# BufferSaver.net
KiCad netlist of a schematic drawn in EAGLE
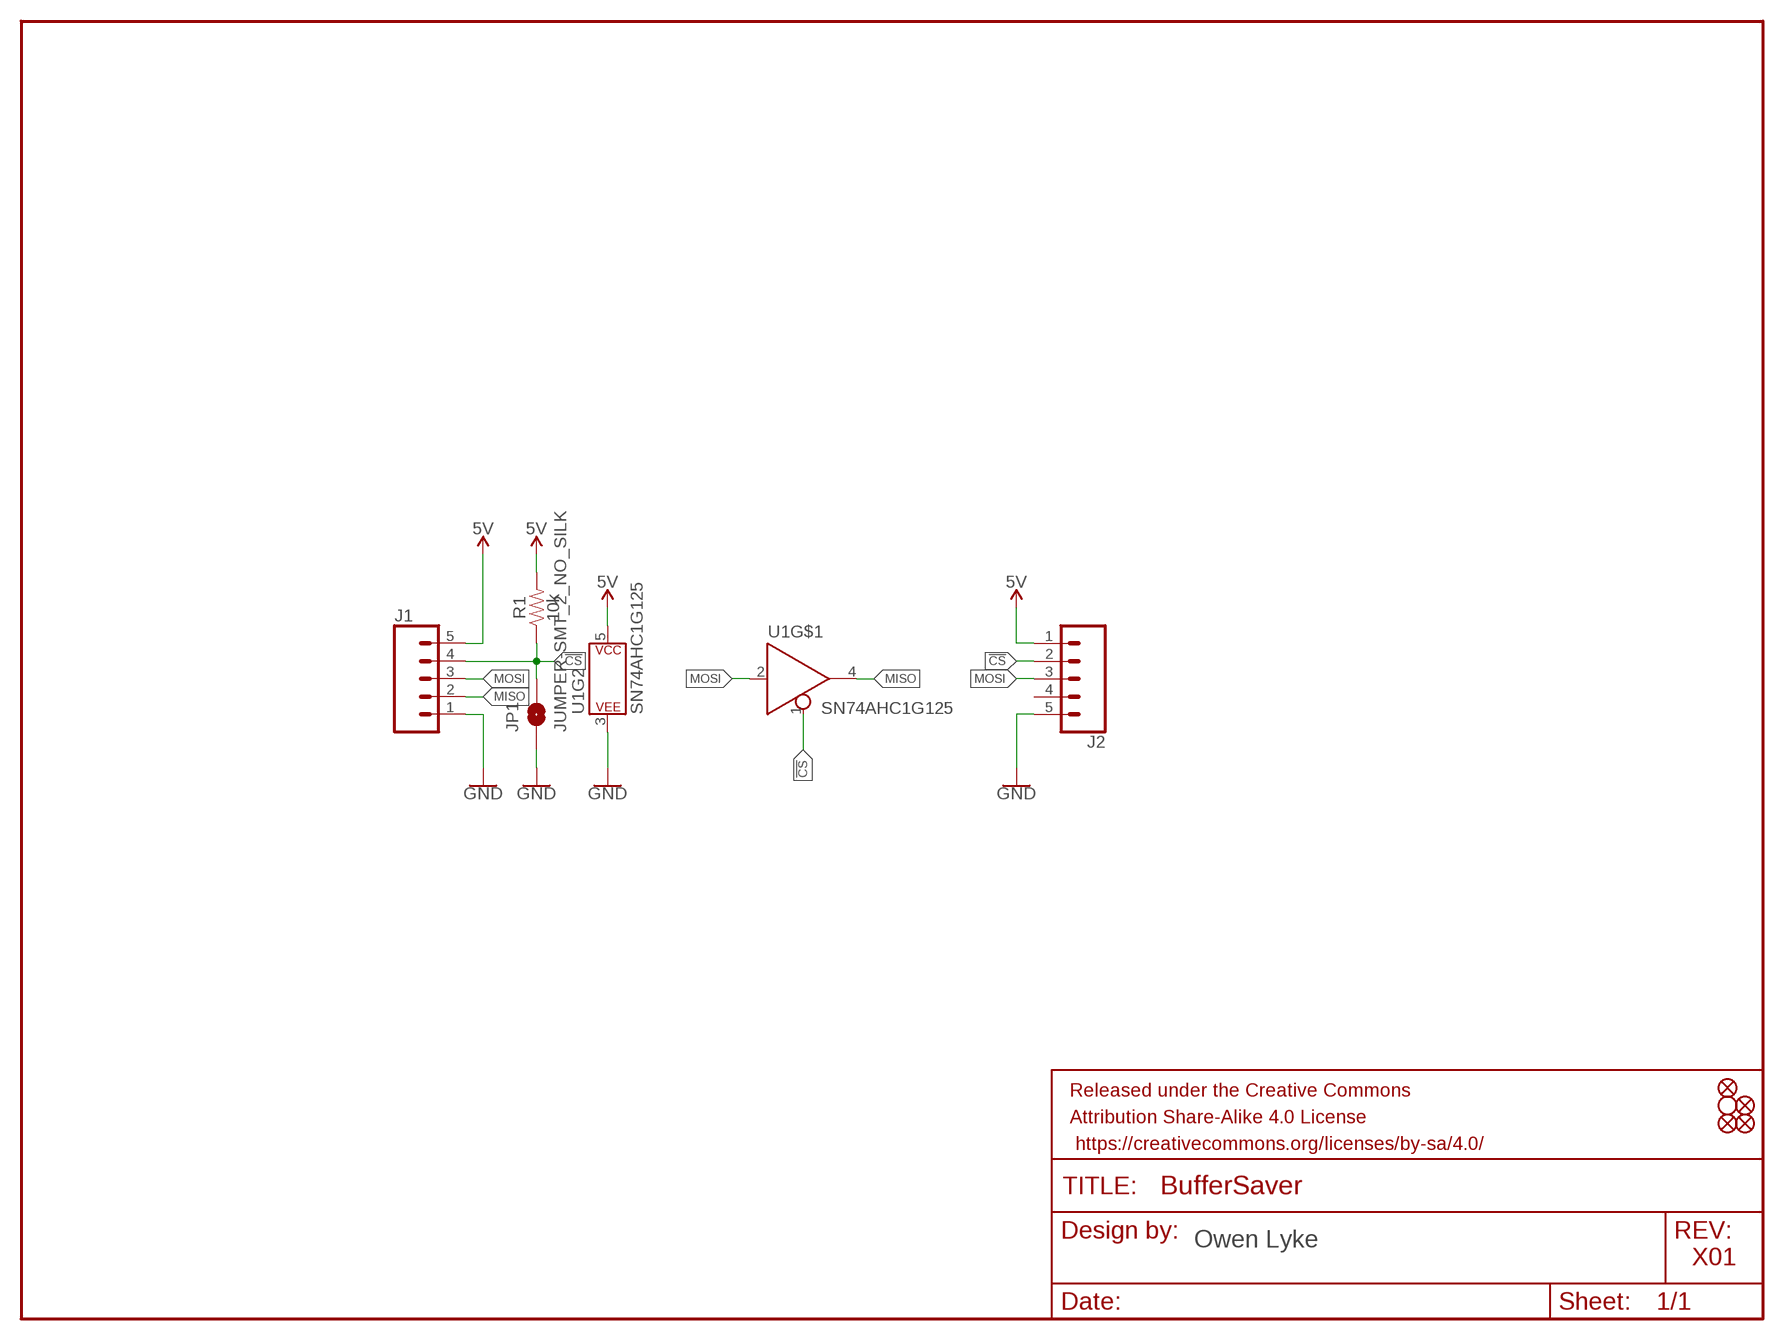
[diagram p0: schematic, sheet 1]

(export (version "E")
  (design (tool "Eeschema 10.0.6"))
  (components
    (comp (ref "FD1")
      (value "FIDUCIAL1X2")
      (footprint "eagle-import:FIDUCIAL-1X2")
      (libsource (lib "eagle-import") (part "FIDUCIAL1X2"))
    )
    (comp (ref "FD2")
      (value "FIDUCIAL1X2")
      (footprint "eagle-import:FIDUCIAL-1X2")
      (libsource (lib "eagle-import") (part "FIDUCIAL1X2"))
    )
    (comp (ref "FD3")
      (value "FIDUCIAL1X2")
      (footprint "eagle-import:FIDUCIAL-1X2")
      (libsource (lib "eagle-import") (part "FIDUCIAL1X2"))
    )
    (comp (ref "FD4")
      (value "FIDUCIAL1X2")
      (footprint "eagle-import:FIDUCIAL-1X2")
      (libsource (lib "eagle-import") (part "FIDUCIAL1X2"))
    )
    (comp (ref "FRAME1")
      (value "FRAME-LETTER")
      (footprint "eagle-import:CREATIVE_COMMONS")
      (libsource (lib "eagle-import") (part "FRAME-LETTER"))
    )
    (comp (ref "H2")
      (value "STAND-OFF")
      (footprint "eagle-import:STAND-OFF")
      (libsource (lib "eagle-import") (part "STAND-OFF"))
    )
    (comp (ref "J1")
      (value "CONN_05NO_SILK")
      (footprint "eagle-import:1X05_NO_SILK")
      (libsource (lib "eagle-import") (part "CONN_05NO_SILK"))
    )
    (comp (ref "J2")
      (value "CONN_05NO_SILK")
      (footprint "eagle-import:1X05_NO_SILK")
      (libsource (lib "eagle-import") (part "CONN_05NO_SILK"))
    )
    (comp (ref "JP1")
      (value "JUMPER-SMT_2_NO_SILK")
      (footprint "eagle-import:SMT-JUMPER_2_NO_SILK")
      (libsource (lib "eagle-import") (part "JUMPER-SMT_2_NO_SILK"))
    )
    (comp (ref "R1")
      (value "10k")
      (footprint "eagle-import:0603")
      (libsource (lib "eagle-import") (part "10KOHM-0603-1/10W-1%"))
    )
    (comp (ref "U1")
      (value "SN74AHC1G125")
      (footprint "eagle-import:SOT23-5")
      (libsource (lib "eagle-import") (part "741G125DAHC"))
    )
  )
  (nets
    (net (code "1") (name "/~{CS}") (class "Default")
      (node (ref "J1") (pin "4") (pinfunction "4_4") (pintype "passive"))
      (node (ref "J2") (pin "2") (pinfunction "2_2") (pintype "passive"))
      (node (ref "JP1") (pin "2") (pinfunction "2_2") (pintype "passive"))
      (node (ref "R1") (pin "1") (pinfunction "1_1") (pintype "passive"))
      (node (ref "U1") (pin "1") (pinfunction "~{EN}_1") (pintype "bidirectional"))
    )
    (net (code "2") (name "5V") (class "Default")
      (node (ref "J1") (pin "5") (pinfunction "5_5") (pintype "passive"))
      (node (ref "J2") (pin "1") (pinfunction "1_1") (pintype "passive"))
      (node (ref "R1") (pin "2") (pinfunction "2_2") (pintype "passive"))
      (node (ref "U1") (pin "5") (pinfunction "P$V+_5") (pintype "bidirectional"))
    )
    (net (code "3") (name "GND") (class "Default")
      (node (ref "J1") (pin "1") (pinfunction "1_1") (pintype "passive"))
      (node (ref "J2") (pin "5") (pinfunction "5_5") (pintype "passive"))
      (node (ref "JP1") (pin "1") (pinfunction "1_1") (pintype "passive"))
      (node (ref "U1") (pin "3") (pinfunction "P$V-_3") (pintype "bidirectional"))
    )
    (net (code "4") (name "MISO") (class "Default")
      (node (ref "J1") (pin "2") (pinfunction "2_2") (pintype "passive"))
      (node (ref "U1") (pin "4") (pinfunction "Y_4") (pintype "bidirectional"))
    )
    (net (code "5") (name "MOSI") (class "Default")
      (node (ref "J1") (pin "3") (pinfunction "3_3") (pintype "passive"))
      (node (ref "J2") (pin "3") (pinfunction "3_3") (pintype "passive"))
      (node (ref "U1") (pin "2") (pinfunction "A_2") (pintype "bidirectional"))
    )
    (net (code "6") (name "unconnected-(J2-Pad4)") (class "Default")
      (node (ref "J2") (pin "4") (pinfunction "4_4") (pintype "passive"))
    )
  )
)
